# PHY.net
KiCad netlist of a schematic drawn in Altium Designer
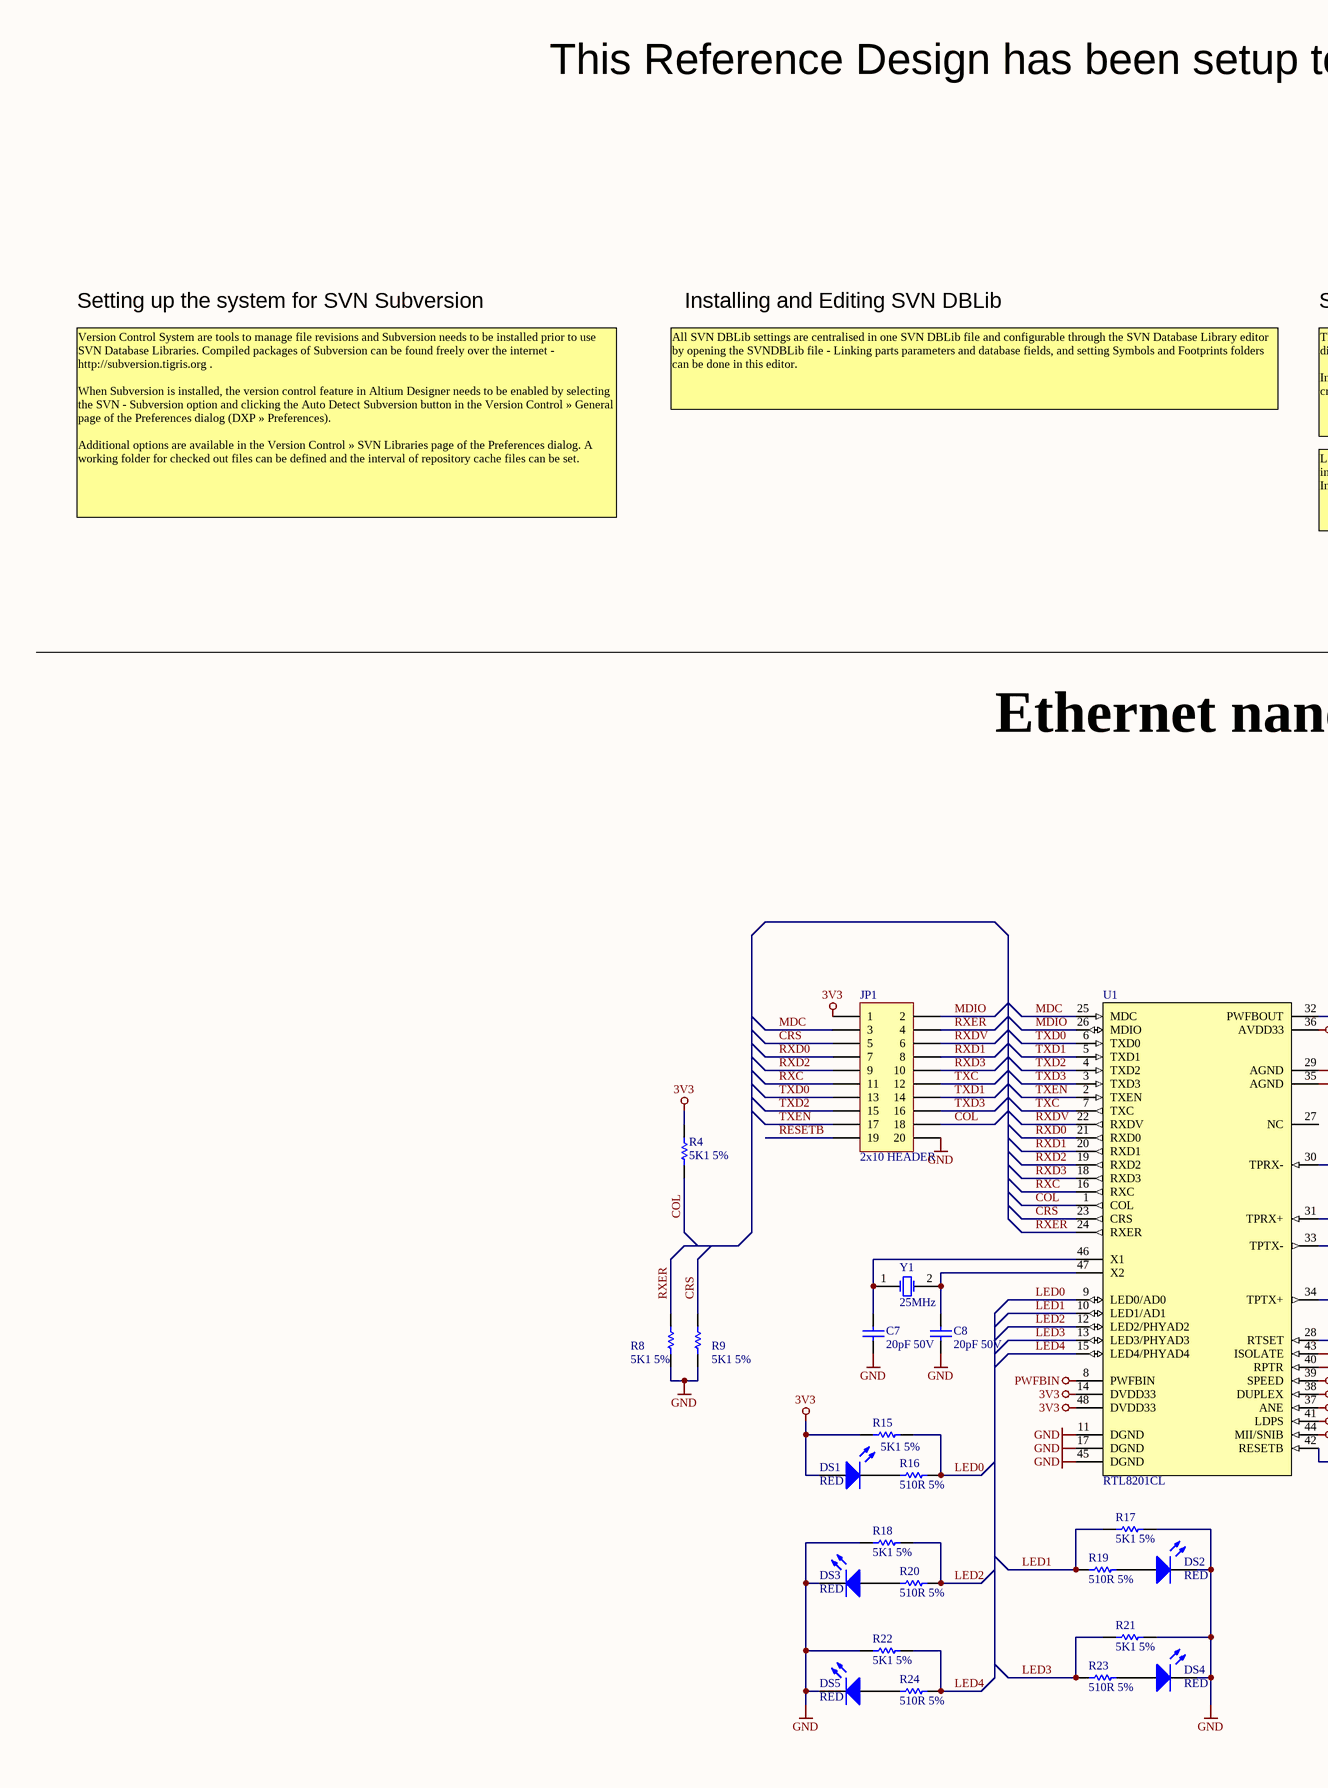
[diagram p0: PHY.SchDoc, left]
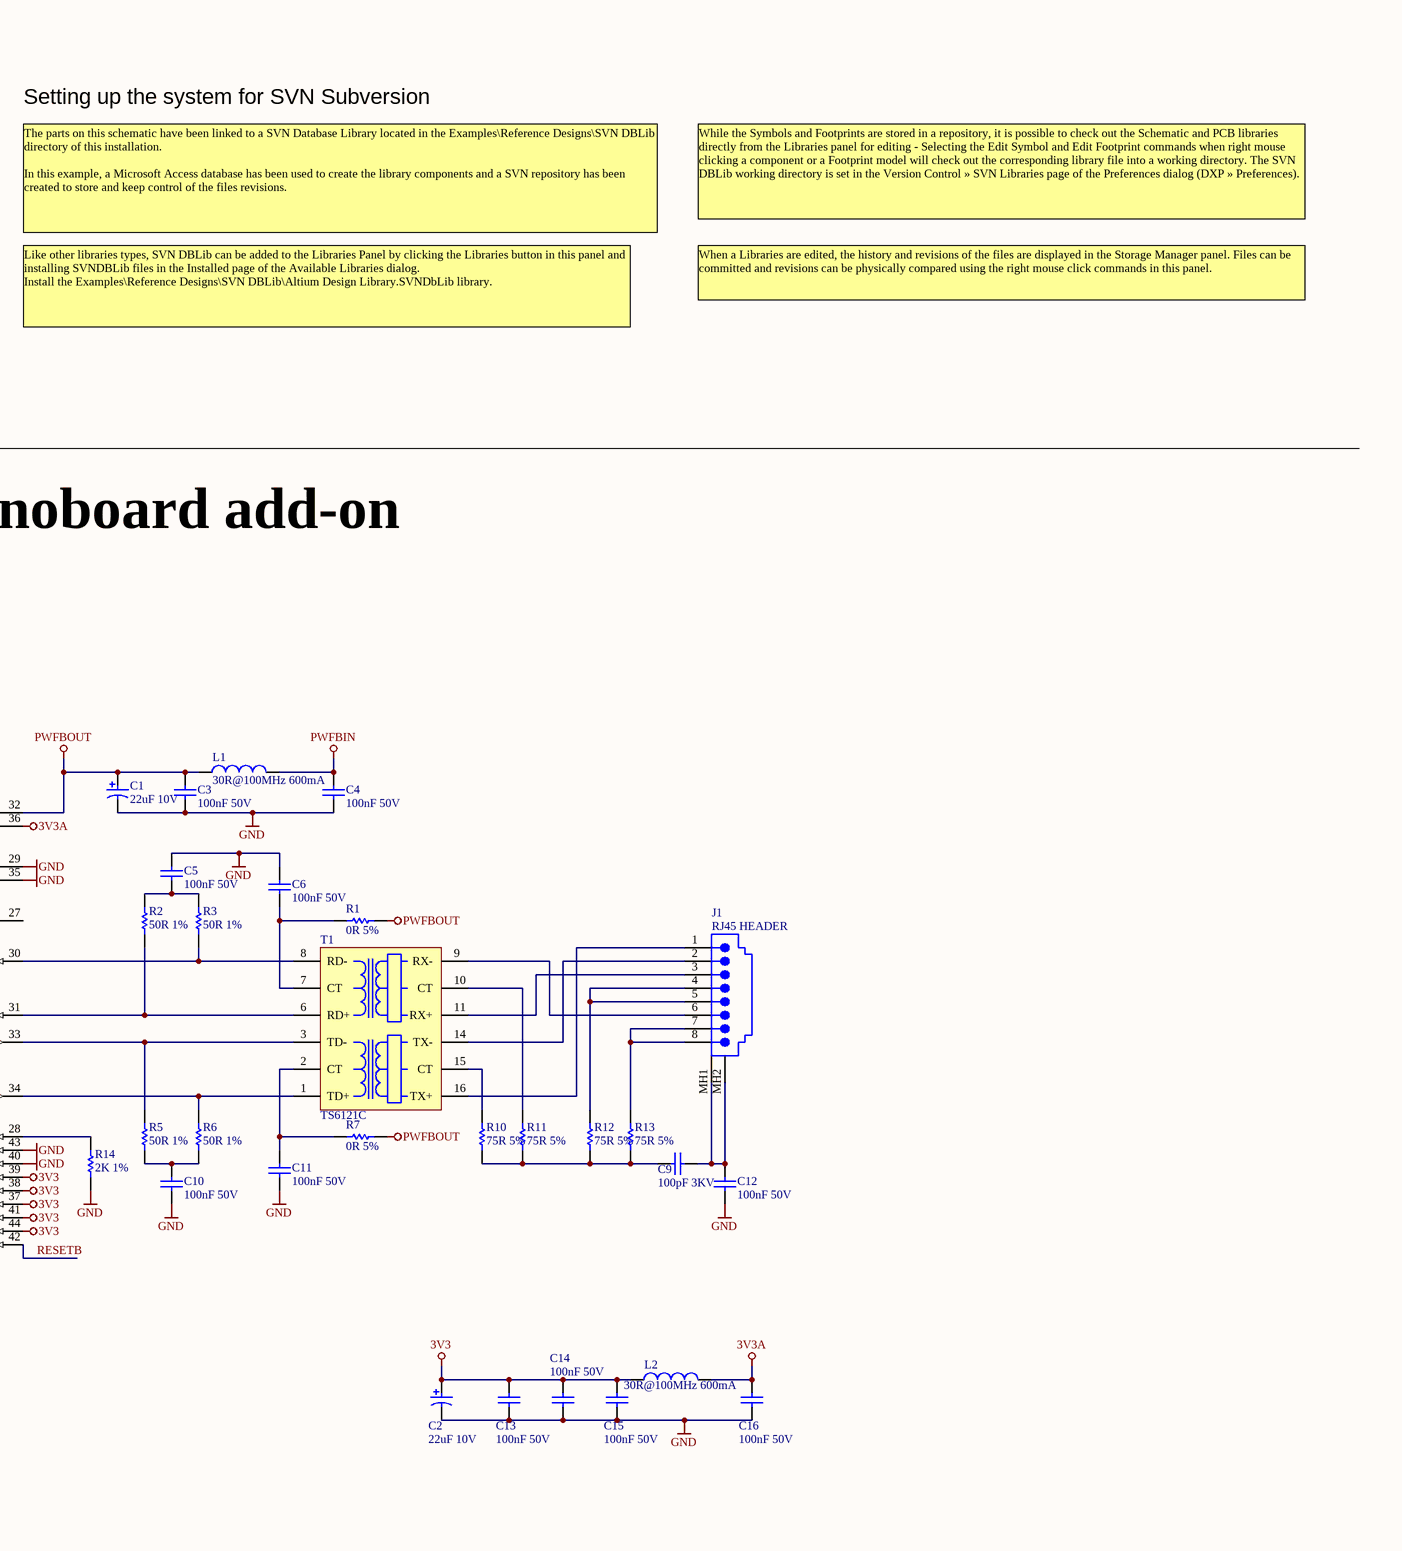
[diagram p1: PHY.SchDoc, right]

(export (version "E")
  (design (tool "Eeschema 10.0.6"))
  (components
    (comp (ref "C1")
      (value "22uF 10V")
      (footprint "CAPC3528")
      (description "Polar Capacitor")
      (libsource (lib "Altium Design Library") (part "CAP-P"))
    )
    (comp (ref "C2")
      (value "22uF 10V")
      (footprint "CAPC3528")
      (description "Polar Capacitor")
      (libsource (lib "Altium Design Library") (part "CAP-P"))
    )
    (comp (ref "C3")
      (value "100nF 50V")
      (footprint "CAPC2012")
      (description "Capacitor")
      (libsource (lib "Altium Design Library") (part "CAP-NP"))
    )
    (comp (ref "C4")
      (value "100nF 50V")
      (footprint "CAPC2012")
      (description "Capacitor")
      (libsource (lib "Altium Design Library") (part "CAP-NP"))
    )
    (comp (ref "C5")
      (value "100nF 50V")
      (footprint "CAPC2012")
      (description "Capacitor")
      (libsource (lib "Altium Design Library") (part "CAP-NP"))
    )
    (comp (ref "C6")
      (value "100nF 50V")
      (footprint "CAPC2012")
      (description "Capacitor")
      (libsource (lib "Altium Design Library") (part "CAP-NP"))
    )
    (comp (ref "C7")
      (value "20pF 50V")
      (footprint "CAPC2012")
      (description "Capacitor")
      (libsource (lib "Altium Design Library") (part "CAP-NP"))
    )
    (comp (ref "C8")
      (value "20pF 50V")
      (footprint "CAPC2012")
      (description "Capacitor")
      (libsource (lib "Altium Design Library") (part "CAP-NP"))
    )
    (comp (ref "C9")
      (value "100pF 3KV")
      (footprint "CAPR7_5-3_6x7_5")
      (description "Capacitor")
      (libsource (lib "Altium Design Library") (part "CAP-NP"))
    )
    (comp (ref "C10")
      (value "100nF 50V")
      (footprint "CAPC2012")
      (description "Capacitor")
      (libsource (lib "Altium Design Library") (part "CAP-NP"))
    )
    (comp (ref "C11")
      (value "100nF 50V")
      (footprint "CAPC2012")
      (description "Capacitor")
      (libsource (lib "Altium Design Library") (part "CAP-NP"))
    )
    (comp (ref "C12")
      (value "100nF 50V")
      (footprint "CAPC2012")
      (description "Capacitor")
      (libsource (lib "Altium Design Library") (part "CAP-NP"))
    )
    (comp (ref "C13")
      (value "100nF 50V")
      (footprint "CAPC2012")
      (description "Capacitor")
      (libsource (lib "Altium Design Library") (part "CAP-NP"))
    )
    (comp (ref "C14")
      (value "100nF 50V")
      (footprint "CAPC2012")
      (description "Capacitor")
      (libsource (lib "Altium Design Library") (part "CAP-NP"))
    )
    (comp (ref "C15")
      (value "100nF 50V")
      (footprint "CAPC2012")
      (description "Capacitor")
      (libsource (lib "Altium Design Library") (part "CAP-NP"))
    )
    (comp (ref "C16")
      (value "100nF 50V")
      (footprint "CAPC2012")
      (description "Capacitor")
      (libsource (lib "Altium Design Library") (part "CAP-NP"))
    )
    (comp (ref "DS1")
      (value "RED")
      (footprint "LED2013")
      (description "Typical GREEN SMD LED Agilent make")
      (libsource (lib "Altium Design Library") (part "DIO-LED-1S"))
    )
    (comp (ref "DS2")
      (value "RED")
      (footprint "LED2013")
      (description "Typical GREEN SMD LED Agilent make")
      (libsource (lib "Altium Design Library") (part "DIO-LED-1S"))
    )
    (comp (ref "DS3")
      (value "RED")
      (footprint "LED2013")
      (description "Typical GREEN SMD LED Agilent make")
      (libsource (lib "Altium Design Library") (part "DIO-LED-1S"))
    )
    (comp (ref "DS4")
      (value "RED")
      (footprint "LED2013")
      (description "Typical GREEN SMD LED Agilent make")
      (libsource (lib "Altium Design Library") (part "DIO-LED-1S"))
    )
    (comp (ref "DS5")
      (value "RED")
      (footprint "LED2013")
      (description "Typical GREEN SMD LED Agilent make")
      (libsource (lib "Altium Design Library") (part "DIO-LED-1S"))
    )
    (comp (ref "J1")
      (value "RJ45 HEADER")
      (footprint "95122-2881")
      (description "Right Angle, Standard Profile, External Shield PCB Jack")
      (libsource (lib "Altium Design Library") (part "CON-RJ45-10-RA"))
    )
    (comp (ref "JP1")
      (value "2x10 HEADER")
      (footprint "HDR2X10")
      (description "Header, 10-Pin, Dual row")
      (libsource (lib "Altium Design Library") (part "CON-HDR-2x10-STR"))
    )
    (comp (ref "L1")
      (value "30R@100MHz 600mA")
      (footprint "INDC2012")
      (description "Ferrite Bead")
      (libsource (lib "Altium Design Library") (part "IND-FER"))
    )
    (comp (ref "L2")
      (value "30R@100MHz 600mA")
      (footprint "INDC2012")
      (description "Ferrite Bead")
      (libsource (lib "Altium Design Library") (part "IND-FER"))
    )
    (comp (ref "R1")
      (value "0R 5%")
      (footprint "RESC2012")
      (description "Resistor")
      (libsource (lib "Altium Design Library") (part "RES"))
    )
    (comp (ref "R2")
      (value "50R 1%")
      (footprint "RESC2012")
      (description "Resistor")
      (libsource (lib "Altium Design Library") (part "RES"))
    )
    (comp (ref "R3")
      (value "50R 1%")
      (footprint "RESC2012")
      (description "Resistor")
      (libsource (lib "Altium Design Library") (part "RES"))
    )
    (comp (ref "R4")
      (value "5K1 5%")
      (footprint "RESC2012")
      (description "Resistor")
      (libsource (lib "Altium Design Library") (part "RES"))
    )
    (comp (ref "R5")
      (value "50R 1%")
      (footprint "RESC2012")
      (description "Resistor")
      (libsource (lib "Altium Design Library") (part "RES"))
    )
    (comp (ref "R6")
      (value "50R 1%")
      (footprint "RESC2012")
      (description "Resistor")
      (libsource (lib "Altium Design Library") (part "RES"))
    )
    (comp (ref "R7")
      (value "0R 5%")
      (footprint "RESC2012")
      (description "Resistor")
      (libsource (lib "Altium Design Library") (part "RES"))
    )
    (comp (ref "R8")
      (value "5K1 5%")
      (footprint "RESC2012")
      (description "Resistor")
      (libsource (lib "Altium Design Library") (part "RES"))
    )
    (comp (ref "R9")
      (value "5K1 5%")
      (footprint "RESC2012")
      (description "Resistor")
      (libsource (lib "Altium Design Library") (part "RES"))
    )
    (comp (ref "R10")
      (value "75R 5%")
      (footprint "RESC2012")
      (description "Resistor")
      (libsource (lib "Altium Design Library") (part "RES"))
    )
    (comp (ref "R11")
      (value "75R 5%")
      (footprint "RESC2012")
      (description "Resistor")
      (libsource (lib "Altium Design Library") (part "RES"))
    )
    (comp (ref "R12")
      (value "75R 5%")
      (footprint "RESC2012")
      (description "Resistor")
      (libsource (lib "Altium Design Library") (part "RES"))
    )
    (comp (ref "R13")
      (value "75R 5%")
      (footprint "RESC2012")
      (description "Resistor")
      (libsource (lib "Altium Design Library") (part "RES"))
    )
    (comp (ref "R14")
      (value "2K 1%")
      (footprint "RESC2012")
      (description "Resistor")
      (libsource (lib "Altium Design Library") (part "RES"))
    )
    (comp (ref "R15")
      (value "5K1 5%")
      (footprint "RESC2012")
      (description "Resistor")
      (libsource (lib "Altium Design Library") (part "RES"))
    )
    (comp (ref "R16")
      (value "510R 5%")
      (footprint "RESC2012")
      (description "Resistor")
      (libsource (lib "Altium Design Library") (part "RES"))
    )
    (comp (ref "R17")
      (value "5K1 5%")
      (footprint "RESC2012")
      (description "Resistor")
      (libsource (lib "Altium Design Library") (part "RES"))
    )
    (comp (ref "R18")
      (value "5K1 5%")
      (footprint "RESC2012")
      (description "Resistor")
      (libsource (lib "Altium Design Library") (part "RES"))
    )
    (comp (ref "R19")
      (value "510R 5%")
      (footprint "RESC2012")
      (description "Resistor")
      (libsource (lib "Altium Design Library") (part "RES"))
    )
    (comp (ref "R20")
      (value "510R 5%")
      (footprint "RESC2012")
      (description "Resistor")
      (libsource (lib "Altium Design Library") (part "RES"))
    )
    (comp (ref "R21")
      (value "5K1 5%")
      (footprint "RESC2012")
      (description "Resistor")
      (libsource (lib "Altium Design Library") (part "RES"))
    )
    (comp (ref "R22")
      (value "5K1 5%")
      (footprint "RESC2012")
      (description "Resistor")
      (libsource (lib "Altium Design Library") (part "RES"))
    )
    (comp (ref "R23")
      (value "510R 5%")
      (footprint "RESC2012")
      (description "Resistor")
      (libsource (lib "Altium Design Library") (part "RES"))
    )
    (comp (ref "R24")
      (value "510R 5%")
      (footprint "RESC2012")
      (description "Resistor")
      (libsource (lib "Altium Design Library") (part "RES"))
    )
    (comp (ref "T1")
      (value "TS6121C")
      (footprint "SOIC127P910-16")
      (description "Bothhand 10/100 BaseT Pulse Transformer")
      (libsource (lib "Altium Design Library") (part "TS6121C"))
    )
    (comp (ref "U1")
      (value "RTL8201CL")
      (footprint "TSQFP50P900X900-48")
      (description "Realtek Ethernet PHY tranceiver")
      (libsource (lib "Altium Design Library") (part "RTL8201CL"))
    )
    (comp (ref "Y1")
      (value "25MHz")
      (footprint "XTAL_HC49SMD 20Mhz  +/-30ppm 20pf")
      (description "Surface Mount Crystal")
      (libsource (lib "Altium Design Library") (part "CRYS"))
    )
  )
  (nets
    (net (code "1") (name "/COL") (class "Default")
      (node (ref "JP1") (pin "18") (pinfunction "18_18") (pintype "passive"))
      (node (ref "R4") (pin "1") (pinfunction "1_1") (pintype "passive"))
      (node (ref "U1") (pin "1") (pinfunction "COL_1") (pintype "output"))
    )
    (net (code "2") (name "/CRS") (class "Default")
      (node (ref "JP1") (pin "5") (pinfunction "5_5") (pintype "passive"))
      (node (ref "R9") (pin "2") (pinfunction "2_2") (pintype "passive"))
      (node (ref "U1") (pin "23") (pinfunction "CRS_23") (pintype "output"))
    )
    (net (code "3") (name "/LED0") (class "Default")
      (node (ref "R15") (pin "1") (pinfunction "1_1") (pintype "passive"))
      (node (ref "R16") (pin "1") (pinfunction "1_1") (pintype "passive"))
      (node (ref "U1") (pin "9") (pinfunction "LED0/AD0_9") (pintype "bidirectional"))
    )
    (net (code "4") (name "/LED1") (class "Default")
      (node (ref "R17") (pin "2") (pinfunction "2_2") (pintype "passive"))
      (node (ref "R19") (pin "1") (pinfunction "1_1") (pintype "passive"))
      (node (ref "U1") (pin "10") (pinfunction "LED1/AD1_10") (pintype "bidirectional"))
    )
    (net (code "5") (name "/LED2") (class "Default")
      (node (ref "R18") (pin "1") (pinfunction "1_1") (pintype "passive"))
      (node (ref "R20") (pin "1") (pinfunction "1_1") (pintype "passive"))
      (node (ref "U1") (pin "12") (pinfunction "LED2/PHYAD2_12") (pintype "bidirectional"))
    )
    (net (code "6") (name "/LED3") (class "Default")
      (node (ref "R21") (pin "2") (pinfunction "2_2") (pintype "passive"))
      (node (ref "R23") (pin "1") (pinfunction "1_1") (pintype "passive"))
      (node (ref "U1") (pin "13") (pinfunction "LED3/PHYAD3_13") (pintype "bidirectional"))
    )
    (net (code "7") (name "/LED4") (class "Default")
      (node (ref "R22") (pin "1") (pinfunction "1_1") (pintype "passive"))
      (node (ref "R24") (pin "1") (pinfunction "1_1") (pintype "passive"))
      (node (ref "U1") (pin "15") (pinfunction "LED4/PHYAD4_15") (pintype "bidirectional"))
    )
    (net (code "8") (name "/MDC") (class "Default")
      (node (ref "JP1") (pin "3") (pinfunction "3_3") (pintype "passive"))
      (node (ref "U1") (pin "25") (pinfunction "MDC_25") (pintype "input"))
    )
    (net (code "9") (name "/MDIO") (class "Default")
      (node (ref "JP1") (pin "2") (pinfunction "2_2") (pintype "passive"))
      (node (ref "U1") (pin "26") (pinfunction "MDIO_26") (pintype "bidirectional"))
    )
    (net (code "10") (name "/RESETB") (class "Default")
      (node (ref "JP1") (pin "19") (pinfunction "19_19") (pintype "passive"))
      (node (ref "U1") (pin "42") (pinfunction "RESETB_42") (pintype "input"))
    )
    (net (code "11") (name "/RXC") (class "Default")
      (node (ref "JP1") (pin "11") (pinfunction "11_11") (pintype "passive"))
      (node (ref "U1") (pin "16") (pinfunction "RXC_16") (pintype "output"))
    )
    (net (code "12") (name "/RXD0") (class "Default")
      (node (ref "JP1") (pin "7") (pinfunction "7_7") (pintype "passive"))
      (node (ref "U1") (pin "21") (pinfunction "RXD0_21") (pintype "output"))
    )
    (net (code "13") (name "/RXD1") (class "Default")
      (node (ref "JP1") (pin "8") (pinfunction "8_8") (pintype "passive"))
      (node (ref "U1") (pin "20") (pinfunction "RXD1_20") (pintype "output"))
    )
    (net (code "14") (name "/RXD2") (class "Default")
      (node (ref "JP1") (pin "9") (pinfunction "9_9") (pintype "passive"))
      (node (ref "U1") (pin "19") (pinfunction "RXD2_19") (pintype "output"))
    )
    (net (code "15") (name "/RXD3") (class "Default")
      (node (ref "JP1") (pin "10") (pinfunction "10_10") (pintype "passive"))
      (node (ref "U1") (pin "18") (pinfunction "RXD3_18") (pintype "output"))
    )
    (net (code "16") (name "/RXDV") (class "Default")
      (node (ref "JP1") (pin "6") (pinfunction "6_6") (pintype "passive"))
      (node (ref "U1") (pin "22") (pinfunction "RXDV_22") (pintype "output"))
    )
    (net (code "17") (name "/RXER") (class "Default")
      (node (ref "JP1") (pin "4") (pinfunction "4_4") (pintype "passive"))
      (node (ref "R8") (pin "2") (pinfunction "2_2") (pintype "passive"))
      (node (ref "U1") (pin "24") (pinfunction "RXER_24") (pintype "output"))
    )
    (net (code "18") (name "/TXC") (class "Default")
      (node (ref "JP1") (pin "12") (pinfunction "12_12") (pintype "passive"))
      (node (ref "U1") (pin "7") (pinfunction "TXC_7") (pintype "output"))
    )
    (net (code "19") (name "/TXD0") (class "Default")
      (node (ref "JP1") (pin "13") (pinfunction "13_13") (pintype "passive"))
      (node (ref "U1") (pin "6") (pinfunction "TXD0_6") (pintype "input"))
    )
    (net (code "20") (name "/TXD1") (class "Default")
      (node (ref "JP1") (pin "14") (pinfunction "14_14") (pintype "passive"))
      (node (ref "U1") (pin "5") (pinfunction "TXD1_5") (pintype "input"))
    )
    (net (code "21") (name "/TXD2") (class "Default")
      (node (ref "JP1") (pin "15") (pinfunction "15_15") (pintype "passive"))
      (node (ref "U1") (pin "4") (pinfunction "TXD2_4") (pintype "input"))
    )
    (net (code "22") (name "/TXD3") (class "Default")
      (node (ref "JP1") (pin "16") (pinfunction "16_16") (pintype "passive"))
      (node (ref "U1") (pin "3") (pinfunction "TXD3_3") (pintype "input"))
    )
    (net (code "23") (name "/TXEN") (class "Default")
      (node (ref "JP1") (pin "17") (pinfunction "17_17") (pintype "passive"))
      (node (ref "U1") (pin "2") (pinfunction "TXEN_2") (pintype "input"))
    )
    (net (code "24") (name "3V3") (class "Default")
      (node (ref "C13") (pin "2") (pinfunction "2_2") (pintype "passive"))
      (node (ref "C14") (pin "2") (pinfunction "2_2") (pintype "passive"))
      (node (ref "C15") (pin "2") (pinfunction "2_2") (pintype "passive"))
      (node (ref "C2") (pin "1") (pinfunction "1_1") (pintype "passive"))
      (node (ref "DS1") (pin "1") (pinfunction "A_1") (pintype "passive"))
      (node (ref "JP1") (pin "1") (pinfunction "1_1") (pintype "passive"))
      (node (ref "L2") (pin "1") (pinfunction "1_1") (pintype "passive"))
      (node (ref "R15") (pin "2") (pinfunction "2_2") (pintype "passive"))
      (node (ref "R4") (pin "2") (pinfunction "2_2") (pintype "passive"))
      (node (ref "U1") (pin "14") (pinfunction "DVDD33_14") (pintype "power_in"))
      (node (ref "U1") (pin "37") (pinfunction "ANE_37") (pintype "input"))
      (node (ref "U1") (pin "38") (pinfunction "DUPLEX_38") (pintype "input"))
      (node (ref "U1") (pin "39") (pinfunction "SPEED_39") (pintype "input"))
      (node (ref "U1") (pin "41") (pinfunction "LDPS_41") (pintype "input"))
      (node (ref "U1") (pin "44") (pinfunction "MII/SNIB_44") (pintype "input"))
      (node (ref "U1") (pin "48") (pinfunction "DVDD33_48") (pintype "power_in"))
    )
    (net (code "25") (name "3V3A") (class "Default")
      (node (ref "C16") (pin "2") (pinfunction "2_2") (pintype "passive"))
      (node (ref "L2") (pin "2") (pinfunction "2_2") (pintype "passive"))
      (node (ref "U1") (pin "36") (pinfunction "AVDD33_36") (pintype "power_in"))
    )
    (net (code "26") (name "GND") (class "Default")
      (node (ref "C1") (pin "2") (pinfunction "2_2") (pintype "passive"))
      (node (ref "C10") (pin "1") (pinfunction "1_1") (pintype "passive"))
      (node (ref "C11") (pin "1") (pinfunction "1_1") (pintype "passive"))
      (node (ref "C12") (pin "1") (pinfunction "1_1") (pintype "passive"))
      (node (ref "C13") (pin "1") (pinfunction "1_1") (pintype "passive"))
      (node (ref "C14") (pin "1") (pinfunction "1_1") (pintype "passive"))
      (node (ref "C15") (pin "1") (pinfunction "1_1") (pintype "passive"))
      (node (ref "C16") (pin "1") (pinfunction "1_1") (pintype "passive"))
      (node (ref "C2") (pin "2") (pinfunction "2_2") (pintype "passive"))
      (node (ref "C3") (pin "1") (pinfunction "1_1") (pintype "passive"))
      (node (ref "C4") (pin "1") (pinfunction "1_1") (pintype "passive"))
      (node (ref "C5") (pin "2") (pinfunction "2_2") (pintype "passive"))
      (node (ref "C6") (pin "1") (pinfunction "1_1") (pintype "passive"))
      (node (ref "C7") (pin "1") (pinfunction "1_1") (pintype "passive"))
      (node (ref "C8") (pin "1") (pinfunction "1_1") (pintype "passive"))
      (node (ref "DS2") (pin "2") (pinfunction "K_2") (pintype "passive"))
      (node (ref "DS3") (pin "2") (pinfunction "K_2") (pintype "passive"))
      (node (ref "DS4") (pin "2") (pinfunction "K_2") (pintype "passive"))
      (node (ref "DS5") (pin "2") (pinfunction "K_2") (pintype "passive"))
      (node (ref "JP1") (pin "20") (pinfunction "20_20") (pintype "passive"))
      (node (ref "R14") (pin "1") (pinfunction "1_1") (pintype "passive"))
      (node (ref "R17") (pin "1") (pinfunction "1_1") (pintype "passive"))
      (node (ref "R18") (pin "2") (pinfunction "2_2") (pintype "passive"))
      (node (ref "R21") (pin "1") (pinfunction "1_1") (pintype "passive"))
      (node (ref "R22") (pin "2") (pinfunction "2_2") (pintype "passive"))
      (node (ref "R8") (pin "1") (pinfunction "1_1") (pintype "passive"))
      (node (ref "R9") (pin "1") (pinfunction "1_1") (pintype "passive"))
      (node (ref "U1") (pin "11") (pinfunction "DGND_11") (pintype "power_in"))
      (node (ref "U1") (pin "17") (pinfunction "DGND_17") (pintype "power_in"))
      (node (ref "U1") (pin "29") (pinfunction "AGND_29") (pintype "power_in"))
      (node (ref "U1") (pin "35") (pinfunction "AGND_35") (pintype "power_in"))
      (node (ref "U1") (pin "40") (pinfunction "RPTR_40") (pintype "input"))
      (node (ref "U1") (pin "43") (pinfunction "ISOLATE_43") (pintype "input"))
      (node (ref "U1") (pin "45") (pinfunction "DGND_45") (pintype "power_in"))
    )
    (net (code "27") (name "Net-(C5-Pad1)") (class "Default")
      (node (ref "C5") (pin "1") (pinfunction "1_1") (pintype "passive"))
      (node (ref "R2") (pin "2") (pinfunction "2_2") (pintype "passive"))
      (node (ref "R3") (pin "2") (pinfunction "2_2") (pintype "passive"))
    )
    (net (code "28") (name "Net-(C6-Pad2)") (class "Default")
      (node (ref "C6") (pin "2") (pinfunction "2_2") (pintype "passive"))
      (node (ref "R1") (pin "1") (pinfunction "1_1") (pintype "passive"))
      (node (ref "T1") (pin "7") (pinfunction "CT_7") (pintype "passive"))
    )
    (net (code "29") (name "Net-(C9-Pad1)") (class "Default")
      (node (ref "C9") (pin "1") (pinfunction "1_1") (pintype "passive"))
      (node (ref "R10") (pin "1") (pinfunction "1_1") (pintype "passive"))
      (node (ref "R11") (pin "1") (pinfunction "1_1") (pintype "passive"))
      (node (ref "R12") (pin "1") (pinfunction "1_1") (pintype "passive"))
      (node (ref "R13") (pin "1") (pinfunction "1_1") (pintype "passive"))
    )
    (net (code "30") (name "Net-(C10-Pad2)") (class "Default")
      (node (ref "C10") (pin "2") (pinfunction "2_2") (pintype "passive"))
      (node (ref "R5") (pin "1") (pinfunction "1_1") (pintype "passive"))
      (node (ref "R6") (pin "1") (pinfunction "1_1") (pintype "passive"))
    )
    (net (code "31") (name "Net-(C11-Pad2)") (class "Default")
      (node (ref "C11") (pin "2") (pinfunction "2_2") (pintype "passive"))
      (node (ref "R7") (pin "1") (pinfunction "1_1") (pintype "passive"))
      (node (ref "T1") (pin "2") (pinfunction "CT_2") (pintype "passive"))
    )
    (net (code "32") (name "Net-(C12-Pad2)") (class "Default")
      (node (ref "C12") (pin "2") (pinfunction "2_2") (pintype "passive"))
      (node (ref "C9") (pin "2") (pinfunction "2_2") (pintype "passive"))
      (node (ref "J1") (pin "MH1") (pinfunction "Shield_MH1") (pintype "passive"))
      (node (ref "J1") (pin "MH2") (pinfunction "Shield_MH2") (pintype "passive"))
    )
    (net (code "33") (name "Net-(DS1-K)") (class "Default")
      (node (ref "DS1") (pin "2") (pinfunction "K_2") (pintype "passive"))
      (node (ref "R16") (pin "2") (pinfunction "2_2") (pintype "passive"))
    )
    (net (code "34") (name "Net-(DS2-A)") (class "Default")
      (node (ref "DS2") (pin "1") (pinfunction "A_1") (pintype "passive"))
      (node (ref "R19") (pin "2") (pinfunction "2_2") (pintype "passive"))
    )
    (net (code "35") (name "Net-(DS3-A)") (class "Default")
      (node (ref "DS3") (pin "1") (pinfunction "A_1") (pintype "passive"))
      (node (ref "R20") (pin "2") (pinfunction "2_2") (pintype "passive"))
    )
    (net (code "36") (name "Net-(DS4-A)") (class "Default")
      (node (ref "DS4") (pin "1") (pinfunction "A_1") (pintype "passive"))
      (node (ref "R23") (pin "2") (pinfunction "2_2") (pintype "passive"))
    )
    (net (code "37") (name "Net-(DS5-A)") (class "Default")
      (node (ref "DS5") (pin "1") (pinfunction "A_1") (pintype "passive"))
      (node (ref "R24") (pin "2") (pinfunction "2_2") (pintype "passive"))
    )
    (net (code "38") (name "Net-(J1-Pad4)") (class "Default")
      (node (ref "J1") (pin "4") (pinfunction "4_4") (pintype "passive"))
      (node (ref "J1") (pin "5") (pinfunction "5_5") (pintype "passive"))
      (node (ref "R12") (pin "2") (pinfunction "2_2") (pintype "passive"))
    )
    (net (code "39") (name "Net-(J1-Pad7)") (class "Default")
      (node (ref "J1") (pin "7") (pinfunction "7_7") (pintype "passive"))
      (node (ref "J1") (pin "8") (pinfunction "8_8") (pintype "passive"))
      (node (ref "R13") (pin "2") (pinfunction "2_2") (pintype "passive"))
    )
    (net (code "40") (name "Net-(R10-Pad2)") (class "Default")
      (node (ref "R10") (pin "2") (pinfunction "2_2") (pintype "passive"))
      (node (ref "T1") (pin "15") (pinfunction "CT_15") (pintype "passive"))
    )
    (net (code "41") (name "Net-(R11-Pad2)") (class "Default")
      (node (ref "R11") (pin "2") (pinfunction "2_2") (pintype "passive"))
      (node (ref "T1") (pin "10") (pinfunction "CT_10") (pintype "passive"))
    )
    (net (code "42") (name "Net-(T1-RD+)") (class "Default")
      (node (ref "R2") (pin "1") (pinfunction "1_1") (pintype "passive"))
      (node (ref "T1") (pin "6") (pinfunction "RD+_6") (pintype "passive"))
      (node (ref "U1") (pin "31") (pinfunction "TPRX+_31") (pintype "input"))
    )
    (net (code "43") (name "Net-(T1-RD-)") (class "Default")
      (node (ref "R3") (pin "1") (pinfunction "1_1") (pintype "passive"))
      (node (ref "T1") (pin "8") (pinfunction "RD-_8") (pintype "passive"))
      (node (ref "U1") (pin "30") (pinfunction "TPRX-_30") (pintype "input"))
    )
    (net (code "44") (name "Net-(T1-RX+)") (class "Default")
      (node (ref "J1") (pin "3") (pinfunction "3_3") (pintype "passive"))
      (node (ref "T1") (pin "11") (pinfunction "RX+_11") (pintype "passive"))
    )
    (net (code "45") (name "Net-(T1-RX-)") (class "Default")
      (node (ref "J1") (pin "6") (pinfunction "6_6") (pintype "passive"))
      (node (ref "T1") (pin "9") (pinfunction "RX-_9") (pintype "passive"))
    )
    (net (code "46") (name "Net-(T1-TD+)") (class "Default")
      (node (ref "R6") (pin "2") (pinfunction "2_2") (pintype "passive"))
      (node (ref "T1") (pin "1") (pinfunction "TD+_1") (pintype "passive"))
      (node (ref "U1") (pin "34") (pinfunction "TPTX+_34") (pintype "output"))
    )
    (net (code "47") (name "Net-(T1-TD-)") (class "Default")
      (node (ref "R5") (pin "2") (pinfunction "2_2") (pintype "passive"))
      (node (ref "T1") (pin "3") (pinfunction "TD-_3") (pintype "passive"))
      (node (ref "U1") (pin "33") (pinfunction "TPTX-_33") (pintype "output"))
    )
    (net (code "48") (name "Net-(T1-TX+)") (class "Default")
      (node (ref "J1") (pin "1") (pinfunction "1_1") (pintype "passive"))
      (node (ref "T1") (pin "16") (pinfunction "TX+_16") (pintype "passive"))
    )
    (net (code "49") (name "Net-(T1-TX-)") (class "Default")
      (node (ref "J1") (pin "2") (pinfunction "2_2") (pintype "passive"))
      (node (ref "T1") (pin "14") (pinfunction "TX-_14") (pintype "passive"))
    )
    (net (code "50") (name "Net-(U1-RTSET)") (class "Default")
      (node (ref "R14") (pin "2") (pinfunction "2_2") (pintype "passive"))
      (node (ref "U1") (pin "28") (pinfunction "RTSET_28") (pintype "input"))
    )
    (net (code "51") (name "Net-(U1-X1)") (class "Default")
      (node (ref "C7") (pin "2") (pinfunction "2_2") (pintype "passive"))
      (node (ref "U1") (pin "46") (pinfunction "X1_46") (pintype "passive"))
      (node (ref "Y1") (pin "1") (pinfunction "OSC1_1") (pintype "passive"))
    )
    (net (code "52") (name "Net-(U1-X2)") (class "Default")
      (node (ref "C8") (pin "2") (pinfunction "2_2") (pintype "passive"))
      (node (ref "U1") (pin "47") (pinfunction "X2_47") (pintype "passive"))
      (node (ref "Y1") (pin "2") (pinfunction "OSC2_2") (pintype "passive"))
    )
    (net (code "53") (name "PWFBIN") (class "Default")
      (node (ref "C4") (pin "2") (pinfunction "2_2") (pintype "passive"))
      (node (ref "L1") (pin "2") (pinfunction "2_2") (pintype "passive"))
      (node (ref "U1") (pin "8") (pinfunction "PWFBIN_8") (pintype "power_in"))
    )
    (net (code "54") (name "PWFBOUT") (class "Default")
      (node (ref "C1") (pin "1") (pinfunction "1_1") (pintype "passive"))
      (node (ref "C3") (pin "2") (pinfunction "2_2") (pintype "passive"))
      (node (ref "L1") (pin "1") (pinfunction "1_1") (pintype "passive"))
      (node (ref "R1") (pin "2") (pinfunction "2_2") (pintype "passive"))
      (node (ref "R7") (pin "2") (pinfunction "2_2") (pintype "passive"))
      (node (ref "U1") (pin "32") (pinfunction "PWFBOUT_32") (pintype "power_in"))
    )
    (net (code "55") (name "unconnected-(U1-NC-Pad27)") (class "Default")
      (node (ref "U1") (pin "27") (pinfunction "NC_27") (pintype "passive"))
    )
  )
)
